# tick-box-1591A-mk-4_0.net
KiCad netlist of a schematic drawn in EAGLE
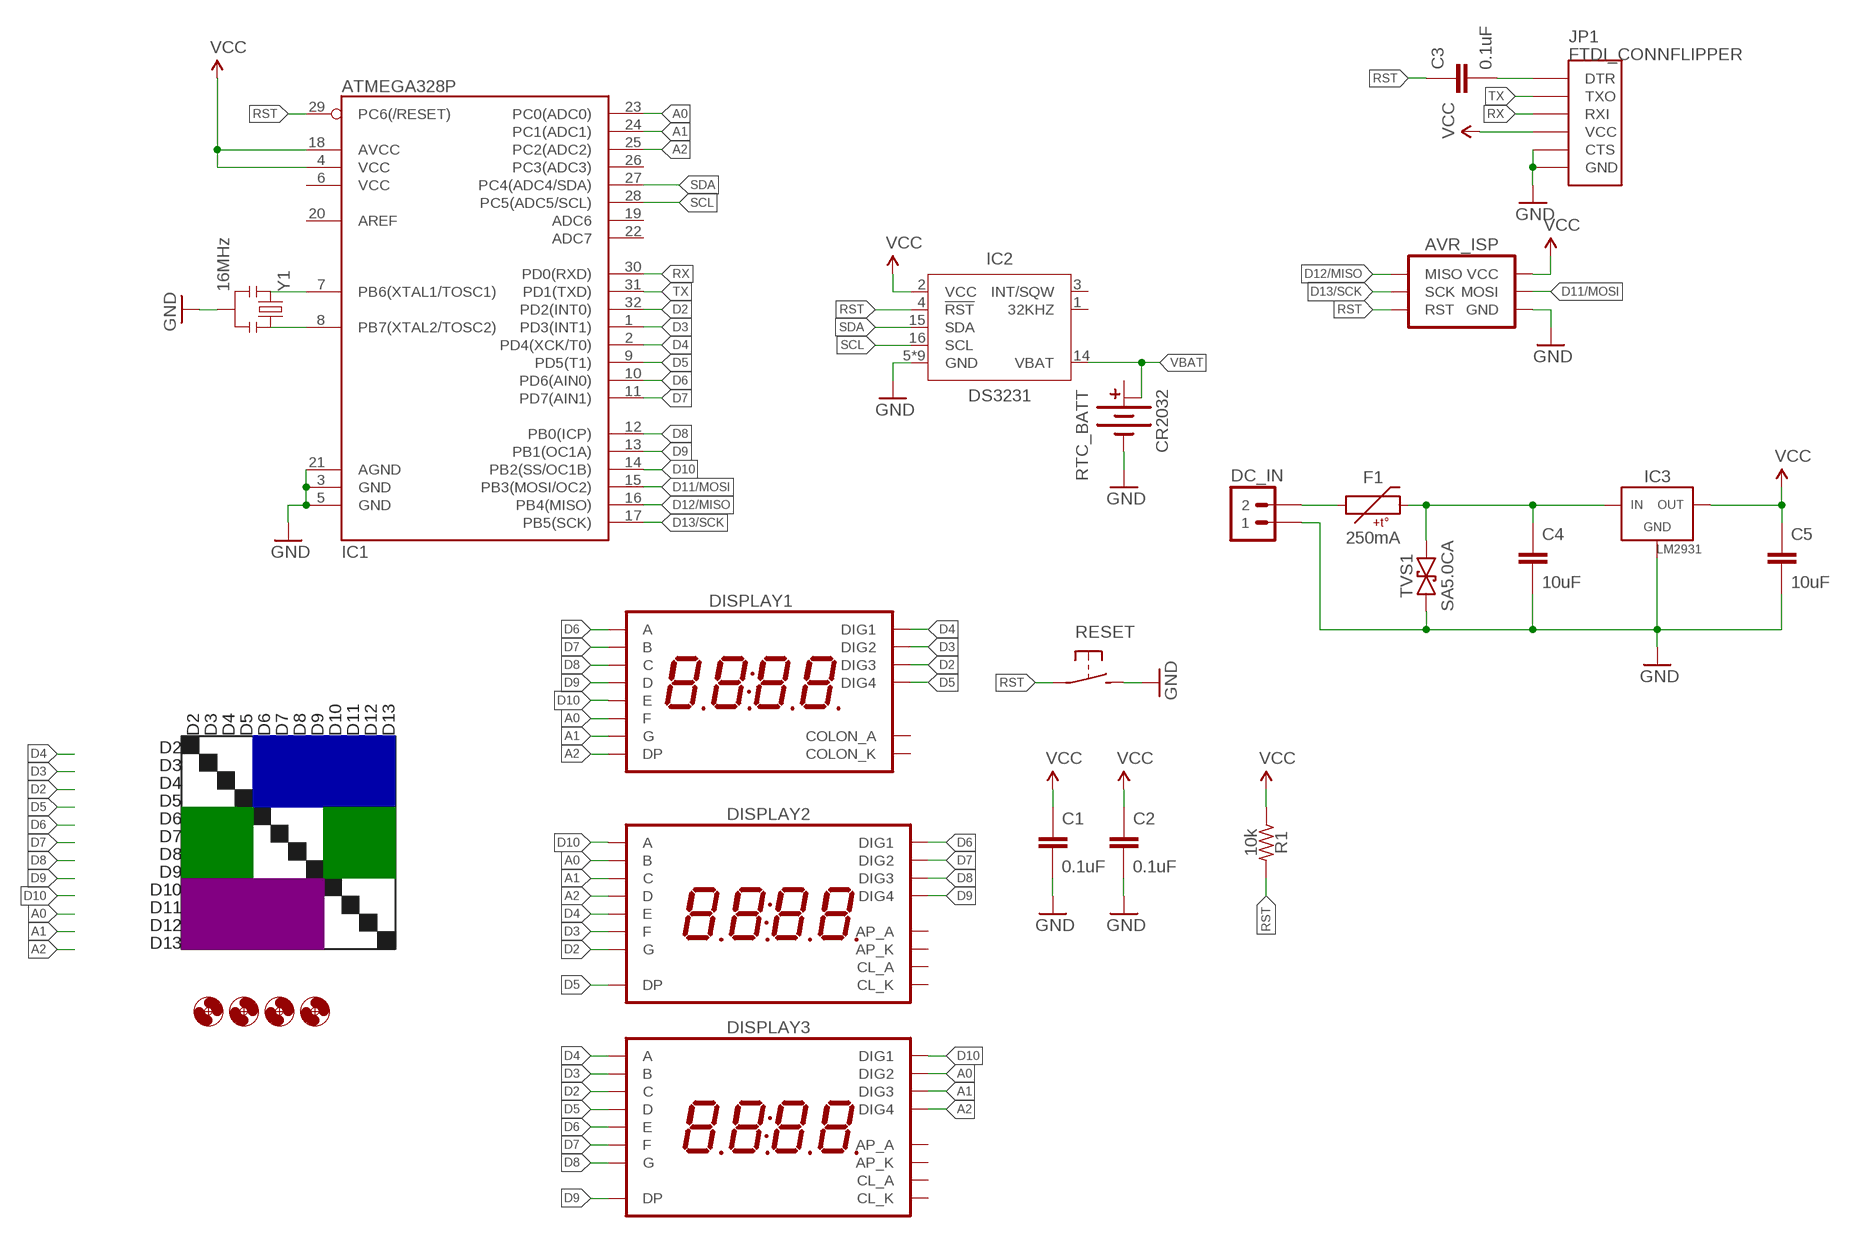
[diagram p0: schematic, sheet 1]

(export (version "E")
  (design (tool "Eeschema 10.0.6"))
  (components
    (comp (ref "AVR_ISP")
      (value "AVR_SPI_PRG_6PTH")
      (footprint "eagle-import:2X3")
      (libsource (lib "eagle-import") (part "AVR_SPI_PRG_6PTH"))
    )
    (comp (ref "C1")
      (value "0.1uF")
      (footprint "eagle-import:C0603")
      (libsource (lib "eagle-import") (part "CAPACITOR-CERAMICC0603"))
    )
    (comp (ref "C2")
      (value "0.1uF")
      (footprint "eagle-import:C0603")
      (libsource (lib "eagle-import") (part "CAPACITOR-CERAMICC0603"))
    )
    (comp (ref "C3")
      (value "0.1uF")
      (footprint "eagle-import:C0603")
      (libsource (lib "eagle-import") (part "CAPACITOR-CERAMICC0603"))
    )
    (comp (ref "C4")
      (value "10uF")
      (footprint "eagle-import:C1206")
      (libsource (lib "eagle-import") (part "CAPACITOR-CERAMICC1206"))
    )
    (comp (ref "C5")
      (value "10uF")
      (footprint "eagle-import:C1206")
      (libsource (lib "eagle-import") (part "CAPACITOR-CERAMICC1206"))
    )
    (comp (ref "DC_IN")
      (value "M02PTH")
      (footprint "eagle-import:1X02")
      (libsource (lib "eagle-import") (part "M02PTH"))
    )
    (comp (ref "DISPLAY1")
      (value "7SEG_4DIGIT_COLON14.2MM-CC-NS")
      (footprint "eagle-import:7SEG_4DIG_NS")
      (libsource (lib "eagle-import") (part "7SEG_4DIGIT_COLON14.2MM-CC-NS"))
    )
    (comp (ref "DISPLAY2")
      (value "7SEG_4DIGIT_COLON_APOS")
      (footprint "eagle-import:7SEG_4DIG_10MM")
      (libsource (lib "eagle-import") (part "7SEG_4DIGIT_COLON_APOS"))
    )
    (comp (ref "DISPLAY3")
      (value "7SEG_4DIGIT_COLON_APOS")
      (footprint "eagle-import:7SEG_4DIG_10MM")
      (libsource (lib "eagle-import") (part "7SEG_4DIGIT_COLON_APOS"))
    )
    (comp (ref "F1")
      (value "250mA")
      (footprint "eagle-import:PTC-1206")
      (libsource (lib "eagle-import") (part "PTCSMD"))
    )
    (comp (ref "H1")
      (value "HOLE#2")
      (footprint "eagle-import:HOLE-#2")
      (libsource (lib "eagle-import") (part "HOLE#2"))
    )
    (comp (ref "H2")
      (value "HOLE#2")
      (footprint "eagle-import:HOLE-#2")
      (libsource (lib "eagle-import") (part "HOLE#2"))
    )
    (comp (ref "H3")
      (value "HOLE#2")
      (footprint "eagle-import:HOLE-#2")
      (libsource (lib "eagle-import") (part "HOLE#2"))
    )
    (comp (ref "H4")
      (value "HOLE#2")
      (footprint "eagle-import:HOLE-#2")
      (libsource (lib "eagle-import") (part "HOLE#2"))
    )
    (comp (ref "IC1")
      (value "ATMEGA328P")
      (footprint "eagle-import:TQFP32-08")
      (libsource (lib "eagle-import") (part "ATMEGA328_SMT"))
    )
    (comp (ref "IC2")
      (value "DS3231")
      (footprint "eagle-import:SO16W")
      (libsource (lib "eagle-import") (part "DS3231"))
    )
    (comp (ref "IC3")
      (value "LM2931")
      (footprint "eagle-import:SO08")
      (libsource (lib "eagle-import") (part "LM2931-FIXED"))
    )
    (comp (ref "JP1")
      (value "FTDI_CONNFLIPPER")
      (footprint "eagle-import:FTDI_CONN_FLIP")
      (libsource (lib "eagle-import") (part "FTDI_CONNFLIPPER"))
    )
    (comp (ref "R1")
      (value "10k")
      (footprint "eagle-import:R0603")
      (libsource (lib "eagle-import") (part "RESISTORR0603"))
    )
    (comp (ref "RESET")
      (value "SPST-NO-TACT3MM-PTH-SMALL-PADS")
      (footprint "eagle-import:DTS-3-SMALL-PADS")
      (libsource (lib "eagle-import") (part "SPST-NO-TACT3MM-PTH-SMALL-PADS"))
    )
    (comp (ref "RTC_BATT")
      (value "CR2032")
      (footprint "eagle-import:BATTCON_20MM_MINE")
      (libsource (lib "eagle-import") (part "BATTERY-COINCR2032_SMD"))
    )
    (comp (ref "TVS1")
      (value "SA5.0CA")
      (footprint "eagle-import:SMA-DIODE-TVS-BIDIR")
      (libsource (lib "eagle-import") (part "TVSSMA"))
    )
    (comp (ref "Y1")
      (value "16MHz")
      (footprint "eagle-import:CSTCE_V_RESONATOR")
      (libsource (lib "eagle-import") (part "RESONATORCSTCE_V"))
    )
  )
  (nets
    (net (code "1") (name "A0") (class "Default")
      (node (ref "DISPLAY1") (pin "P$12") (pinfunction "F_P$12") (pintype "passive"))
      (node (ref "DISPLAY2") (pin "16") (pinfunction "B_16") (pintype "passive"))
      (node (ref "DISPLAY3") (pin "2") (pinfunction "DIG2_2") (pintype "passive"))
      (node (ref "IC1") (pin "23") (pinfunction "PC0(ADC0)_23") (pintype "bidirectional"))
    )
    (net (code "2") (name "A1") (class "Default")
      (node (ref "DISPLAY1") (pin "P$5") (pinfunction "G_P$5") (pintype "passive"))
      (node (ref "DISPLAY2") (pin "13") (pinfunction "C_13") (pintype "passive"))
      (node (ref "DISPLAY3") (pin "6") (pinfunction "DIG3_6") (pintype "passive"))
      (node (ref "IC1") (pin "24") (pinfunction "PC1(ADC1)_24") (pintype "bidirectional"))
    )
    (net (code "3") (name "A2") (class "Default")
      (node (ref "DISPLAY1") (pin "P$3") (pinfunction "DP_P$3") (pintype "passive"))
      (node (ref "DISPLAY2") (pin "3") (pinfunction "D_3") (pintype "passive"))
      (node (ref "DISPLAY3") (pin "8") (pinfunction "DIG4_8") (pintype "passive"))
      (node (ref "IC1") (pin "25") (pinfunction "PC2(ADC2)_25") (pintype "bidirectional"))
    )
    (net (code "4") (name "D2") (class "Default")
      (node (ref "DISPLAY1") (pin "P$10") (pinfunction "DIG3_P$10") (pintype "passive"))
      (node (ref "DISPLAY2") (pin "15") (pinfunction "G_15") (pintype "passive"))
      (node (ref "DISPLAY3") (pin "13") (pinfunction "C_13") (pintype "passive"))
      (node (ref "IC1") (pin "32") (pinfunction "PD2(INT0)_32") (pintype "bidirectional"))
    )
    (net (code "5") (name "D3") (class "Default")
      (node (ref "DISPLAY1") (pin "P$11") (pinfunction "DIG2_P$11") (pintype "passive"))
      (node (ref "DISPLAY2") (pin "11") (pinfunction "F_11") (pintype "passive"))
      (node (ref "DISPLAY3") (pin "16") (pinfunction "B_16") (pintype "passive"))
      (node (ref "IC1") (pin "1") (pinfunction "PD3(INT1)_1") (pintype "bidirectional"))
    )
    (net (code "6") (name "D4") (class "Default")
      (node (ref "DISPLAY1") (pin "P$14") (pinfunction "DIG1_P$14") (pintype "passive"))
      (node (ref "DISPLAY2") (pin "5") (pinfunction "E_5") (pintype "passive"))
      (node (ref "DISPLAY3") (pin "14") (pinfunction "A_14") (pintype "passive"))
      (node (ref "IC1") (pin "2") (pinfunction "PD4(XCK/T0)_2") (pintype "bidirectional"))
    )
    (net (code "7") (name "D5") (class "Default")
      (node (ref "DISPLAY1") (pin "P$6") (pinfunction "DIG4_P$6") (pintype "passive"))
      (node (ref "DISPLAY2") (pin "7") (pinfunction "DP_7") (pintype "passive"))
      (node (ref "DISPLAY3") (pin "3") (pinfunction "D_3") (pintype "passive"))
      (node (ref "IC1") (pin "9") (pinfunction "PD5(T1)_9") (pintype "bidirectional"))
    )
    (net (code "8") (name "D6") (class "Default")
      (node (ref "DISPLAY1") (pin "P$13") (pinfunction "A_P$13") (pintype "passive"))
      (node (ref "DISPLAY2") (pin "1") (pinfunction "DIG1_1") (pintype "passive"))
      (node (ref "DISPLAY3") (pin "5") (pinfunction "E_5") (pintype "passive"))
      (node (ref "IC1") (pin "10") (pinfunction "PD6(AIN0)_10") (pintype "bidirectional"))
    )
    (net (code "9") (name "D7") (class "Default")
      (node (ref "DISPLAY1") (pin "P$9") (pinfunction "B_P$9") (pintype "passive"))
      (node (ref "DISPLAY2") (pin "2") (pinfunction "DIG2_2") (pintype "passive"))
      (node (ref "DISPLAY3") (pin "11") (pinfunction "F_11") (pintype "passive"))
      (node (ref "IC1") (pin "11") (pinfunction "PD7(AIN1)_11") (pintype "bidirectional"))
    )
    (net (code "10") (name "D8") (class "Default")
      (node (ref "DISPLAY1") (pin "P$4") (pinfunction "C_P$4") (pintype "passive"))
      (node (ref "DISPLAY2") (pin "6") (pinfunction "DIG3_6") (pintype "passive"))
      (node (ref "DISPLAY3") (pin "15") (pinfunction "G_15") (pintype "passive"))
      (node (ref "IC1") (pin "12") (pinfunction "PB0(ICP)_12") (pintype "bidirectional"))
    )
    (net (code "11") (name "D9") (class "Default")
      (node (ref "DISPLAY1") (pin "P$2") (pinfunction "D_P$2") (pintype "passive"))
      (node (ref "DISPLAY2") (pin "8") (pinfunction "DIG4_8") (pintype "passive"))
      (node (ref "DISPLAY3") (pin "7") (pinfunction "DP_7") (pintype "passive"))
      (node (ref "IC1") (pin "13") (pinfunction "PB1(OC1A)_13") (pintype "bidirectional"))
    )
    (net (code "12") (name "D10") (class "Default")
      (node (ref "DISPLAY1") (pin "P$1") (pinfunction "E_P$1") (pintype "passive"))
      (node (ref "DISPLAY2") (pin "14") (pinfunction "A_14") (pintype "passive"))
      (node (ref "DISPLAY3") (pin "1") (pinfunction "DIG1_1") (pintype "passive"))
      (node (ref "IC1") (pin "14") (pinfunction "PB2(SS/OC1B)_14") (pintype "bidirectional"))
    )
    (net (code "13") (name "D11{slash}MOSI") (class "Default")
      (node (ref "AVR_ISP") (pin "4") (pinfunction "MOSI_4") (pintype "passive"))
      (node (ref "IC1") (pin "15") (pinfunction "PB3(MOSI/OC2)_15") (pintype "bidirectional"))
    )
    (net (code "14") (name "D12{slash}MISO") (class "Default")
      (node (ref "AVR_ISP") (pin "1") (pinfunction "MISO_1") (pintype "passive"))
      (node (ref "IC1") (pin "16") (pinfunction "PB4(MISO)_16") (pintype "bidirectional"))
    )
    (net (code "15") (name "D13{slash}SCK") (class "Default")
      (node (ref "AVR_ISP") (pin "3") (pinfunction "SCK_3") (pintype "passive"))
      (node (ref "IC1") (pin "17") (pinfunction "PB5(SCK)_17") (pintype "bidirectional"))
    )
    (net (code "16") (name "GND") (class "Default")
      (node (ref "AVR_ISP") (pin "6") (pinfunction "GND_6") (pintype "passive"))
      (node (ref "C1") (pin "2") (pinfunction "2_2") (pintype "passive"))
      (node (ref "C2") (pin "2") (pinfunction "2_2") (pintype "passive"))
      (node (ref "C4") (pin "2") (pinfunction "2_2") (pintype "passive"))
      (node (ref "C5") (pin "2") (pinfunction "2_2") (pintype "passive"))
      (node (ref "DC_IN") (pin "1") (pinfunction "1_1") (pintype "passive"))
      (node (ref "IC1") (pin "21") (pinfunction "AGND_21") (pintype "bidirectional"))
      (node (ref "IC1") (pin "3") (pinfunction "GND_3") (pintype "bidirectional"))
      (node (ref "IC1") (pin "5") (pinfunction "GND_5") (pintype "bidirectional"))
      (node (ref "IC2") (pin "10") (pinfunction "GND_10") (pintype "bidirectional"))
      (node (ref "IC2") (pin "11") (pinfunction "GND_11") (pintype "bidirectional"))
      (node (ref "IC2") (pin "12") (pinfunction "GND_12") (pintype "bidirectional"))
      (node (ref "IC2") (pin "13") (pinfunction "GND_13") (pintype "bidirectional"))
      (node (ref "IC2") (pin "5") (pinfunction "GND_5") (pintype "bidirectional"))
      (node (ref "IC2") (pin "6") (pinfunction "GND_6") (pintype "bidirectional"))
      (node (ref "IC2") (pin "7") (pinfunction "GND_7") (pintype "bidirectional"))
      (node (ref "IC2") (pin "8") (pinfunction "GND_8") (pintype "bidirectional"))
      (node (ref "IC2") (pin "9") (pinfunction "GND_9") (pintype "bidirectional"))
      (node (ref "IC3") (pin "2") (pinfunction "GND_2") (pintype "bidirectional"))
      (node (ref "IC3") (pin "3") (pinfunction "GND_3") (pintype "bidirectional"))
      (node (ref "IC3") (pin "4") (pinfunction "GND_4") (pintype "bidirectional"))
      (node (ref "IC3") (pin "5") (pinfunction "GND_5") (pintype "bidirectional"))
      (node (ref "IC3") (pin "6") (pinfunction "GND_6") (pintype "bidirectional"))
      (node (ref "IC3") (pin "7") (pinfunction "GND_7") (pintype "bidirectional"))
      (node (ref "JP1") (pin "CTS") (pinfunction "CTS_CTS") (pintype "bidirectional"))
      (node (ref "JP1") (pin "GND") (pinfunction "GND_GND") (pintype "bidirectional"))
      (node (ref "RESET") (pin "2") (pinfunction "2_2") (pintype "passive"))
      (node (ref "RTC_BATT") (pin "BOTTOM") (pinfunction "-_BOTTOM") (pintype "bidirectional"))
      (node (ref "TVS1") (pin "1") (pinfunction "1_1") (pintype "passive"))
      (node (ref "Y1") (pin "2") (pinfunction "2_2") (pintype "passive"))
    )
    (net (code "17") (name "Net-(C3-Pad2)") (class "Default")
      (node (ref "C3") (pin "2") (pinfunction "2_2") (pintype "passive"))
      (node (ref "JP1") (pin "DTR") (pinfunction "DTR_DTR") (pintype "bidirectional"))
    )
    (net (code "18") (name "Net-(DC_IN-Pad2)") (class "Default")
      (node (ref "DC_IN") (pin "2") (pinfunction "2_2") (pintype "passive"))
      (node (ref "F1") (pin "1") (pinfunction "1_1") (pintype "passive"))
    )
    (net (code "19") (name "Net-(IC1-PB6(XTAL1{slash}TOSC1))") (class "Default")
      (node (ref "IC1") (pin "7") (pinfunction "PB6(XTAL1/TOSC1)_7") (pintype "bidirectional"))
      (node (ref "Y1") (pin "3") (pinfunction "3_3") (pintype "passive"))
    )
    (net (code "20") (name "Net-(IC1-PB7(XTAL2{slash}TOSC2))") (class "Default")
      (node (ref "IC1") (pin "8") (pinfunction "PB7(XTAL2/TOSC2)_8") (pintype "bidirectional"))
      (node (ref "Y1") (pin "1") (pinfunction "1_1") (pintype "passive"))
    )
    (net (code "21") (name "Net-(IC3-IN)") (class "Default")
      (node (ref "C4") (pin "1") (pinfunction "1_1") (pintype "passive"))
      (node (ref "F1") (pin "2") (pinfunction "2_2") (pintype "passive"))
      (node (ref "IC3") (pin "8") (pinfunction "IN_8") (pintype "bidirectional"))
      (node (ref "TVS1") (pin "2") (pinfunction "2_2") (pintype "passive"))
    )
    (net (code "22") (name "RST") (class "Default")
      (node (ref "AVR_ISP") (pin "5") (pinfunction "RST_5") (pintype "passive"))
      (node (ref "C3") (pin "1") (pinfunction "1_1") (pintype "passive"))
      (node (ref "IC1") (pin "29") (pinfunction "PC6(/RESET)_29") (pintype "bidirectional"))
      (node (ref "IC2") (pin "4") (pinfunction "~{RST}_4") (pintype "bidirectional"))
      (node (ref "R1") (pin "2") (pinfunction "2_2") (pintype "passive"))
      (node (ref "RESET") (pin "1") (pinfunction "1_1") (pintype "passive"))
    )
    (net (code "23") (name "RX") (class "Default")
      (node (ref "IC1") (pin "30") (pinfunction "PD0(RXD)_30") (pintype "bidirectional"))
      (node (ref "JP1") (pin "RXI") (pinfunction "RXI_RXI") (pintype "bidirectional"))
    )
    (net (code "24") (name "SCL") (class "Default")
      (node (ref "IC1") (pin "28") (pinfunction "PC5(ADC5/SCL)_28") (pintype "bidirectional"))
      (node (ref "IC2") (pin "16") (pinfunction "SCL_16") (pintype "bidirectional"))
    )
    (net (code "25") (name "SDA") (class "Default")
      (node (ref "IC1") (pin "27") (pinfunction "PC4(ADC4/SDA)_27") (pintype "bidirectional"))
      (node (ref "IC2") (pin "15") (pinfunction "SDA_15") (pintype "bidirectional"))
    )
    (net (code "26") (name "TX") (class "Default")
      (node (ref "IC1") (pin "31") (pinfunction "PD1(TXD)_31") (pintype "bidirectional"))
      (node (ref "JP1") (pin "TXO") (pinfunction "TXO_TXO") (pintype "bidirectional"))
    )
    (net (code "27") (name "VBAT") (class "Default")
      (node (ref "IC2") (pin "14") (pinfunction "VBAT_14") (pintype "bidirectional"))
      (node (ref "RTC_BATT") (pin "TOP@2") (pinfunction "+1_TOP@2") (pintype "bidirectional"))
    )
    (net (code "28") (name "VCC") (class "Default")
      (node (ref "AVR_ISP") (pin "2") (pinfunction "VCC_2") (pintype "passive"))
      (node (ref "C1") (pin "1") (pinfunction "1_1") (pintype "passive"))
      (node (ref "C2") (pin "1") (pinfunction "1_1") (pintype "passive"))
      (node (ref "C5") (pin "1") (pinfunction "1_1") (pintype "passive"))
      (node (ref "IC1") (pin "18") (pinfunction "AVCC_18") (pintype "bidirectional"))
      (node (ref "IC1") (pin "4") (pinfunction "VCC_4") (pintype "bidirectional"))
      (node (ref "IC2") (pin "2") (pinfunction "VCC_2") (pintype "bidirectional"))
      (node (ref "IC3") (pin "1") (pinfunction "OUT_1") (pintype "bidirectional"))
      (node (ref "JP1") (pin "VCC") (pinfunction "VCC_VCC") (pintype "bidirectional"))
      (node (ref "R1") (pin "1") (pinfunction "1_1") (pintype "passive"))
    )
    (net (code "29") (name "unconnected-(DISPLAY1-COLON_A-PadP$8)") (class "Default")
      (node (ref "DISPLAY1") (pin "P$8") (pinfunction "COLON_A_P$8") (pintype "passive"))
    )
    (net (code "30") (name "unconnected-(DISPLAY1-COLON_K-PadP$7)") (class "Default")
      (node (ref "DISPLAY1") (pin "P$7") (pinfunction "COLON_K_P$7") (pintype "passive"))
    )
    (net (code "31") (name "unconnected-(DISPLAY2-AP_A-Pad10)") (class "Default")
      (node (ref "DISPLAY2") (pin "10") (pinfunction "AP_A_10") (pintype "bidirectional"))
    )
    (net (code "32") (name "unconnected-(DISPLAY2-AP_K-Pad9)") (class "Default")
      (node (ref "DISPLAY2") (pin "9") (pinfunction "AP_K_9") (pintype "bidirectional"))
    )
    (net (code "33") (name "unconnected-(DISPLAY2-CL_A-Pad4)") (class "Default")
      (node (ref "DISPLAY2") (pin "4") (pinfunction "CL_A_4") (pintype "passive"))
    )
    (net (code "34") (name "unconnected-(DISPLAY2-CL_K-Pad12)") (class "Default")
      (node (ref "DISPLAY2") (pin "12") (pinfunction "CL_K_12") (pintype "passive"))
    )
    (net (code "35") (name "unconnected-(DISPLAY3-AP_A-Pad10)") (class "Default")
      (node (ref "DISPLAY3") (pin "10") (pinfunction "AP_A_10") (pintype "bidirectional"))
    )
    (net (code "36") (name "unconnected-(DISPLAY3-AP_K-Pad9)") (class "Default")
      (node (ref "DISPLAY3") (pin "9") (pinfunction "AP_K_9") (pintype "bidirectional"))
    )
    (net (code "37") (name "unconnected-(DISPLAY3-CL_A-Pad4)") (class "Default")
      (node (ref "DISPLAY3") (pin "4") (pinfunction "CL_A_4") (pintype "passive"))
    )
    (net (code "38") (name "unconnected-(DISPLAY3-CL_K-Pad12)") (class "Default")
      (node (ref "DISPLAY3") (pin "12") (pinfunction "CL_K_12") (pintype "passive"))
    )
    (net (code "39") (name "unconnected-(IC1-ADC6-Pad19)") (class "Default")
      (node (ref "IC1") (pin "19") (pinfunction "ADC6_19") (pintype "bidirectional"))
    )
    (net (code "40") (name "unconnected-(IC1-ADC7-Pad22)") (class "Default")
      (node (ref "IC1") (pin "22") (pinfunction "ADC7_22") (pintype "bidirectional"))
    )
    (net (code "41") (name "unconnected-(IC1-AREF-Pad20)") (class "Default")
      (node (ref "IC1") (pin "20") (pinfunction "AREF_20") (pintype "bidirectional"))
    )
    (net (code "42") (name "unconnected-(IC1-PC3(ADC3)-Pad26)") (class "Default")
      (node (ref "IC1") (pin "26") (pinfunction "PC3(ADC3)_26") (pintype "bidirectional"))
    )
    (net (code "43") (name "unconnected-(IC1-VCC-Pad6)") (class "Default")
      (node (ref "IC1") (pin "6") (pinfunction "VCC_6") (pintype "bidirectional"))
    )
    (net (code "44") (name "unconnected-(IC2-32KHZ-Pad1)") (class "Default")
      (node (ref "IC2") (pin "1") (pinfunction "32KHZ_1") (pintype "bidirectional"))
    )
    (net (code "45") (name "unconnected-(IC2-INT{slash}SQW-Pad3)") (class "Default")
      (node (ref "IC2") (pin "3") (pinfunction "INT/SQW_3") (pintype "bidirectional"))
    )
    (net (code "46") (name "unconnected-(RTC_BATT-+-PadTOP@1)") (class "Default")
      (node (ref "RTC_BATT") (pin "TOP@1") (pinfunction "+_TOP@1") (pintype "bidirectional"))
    )
  )
)
